# IOMOD-AD5593R-v2_0.net
KiCad netlist of a schematic drawn in EAGLE
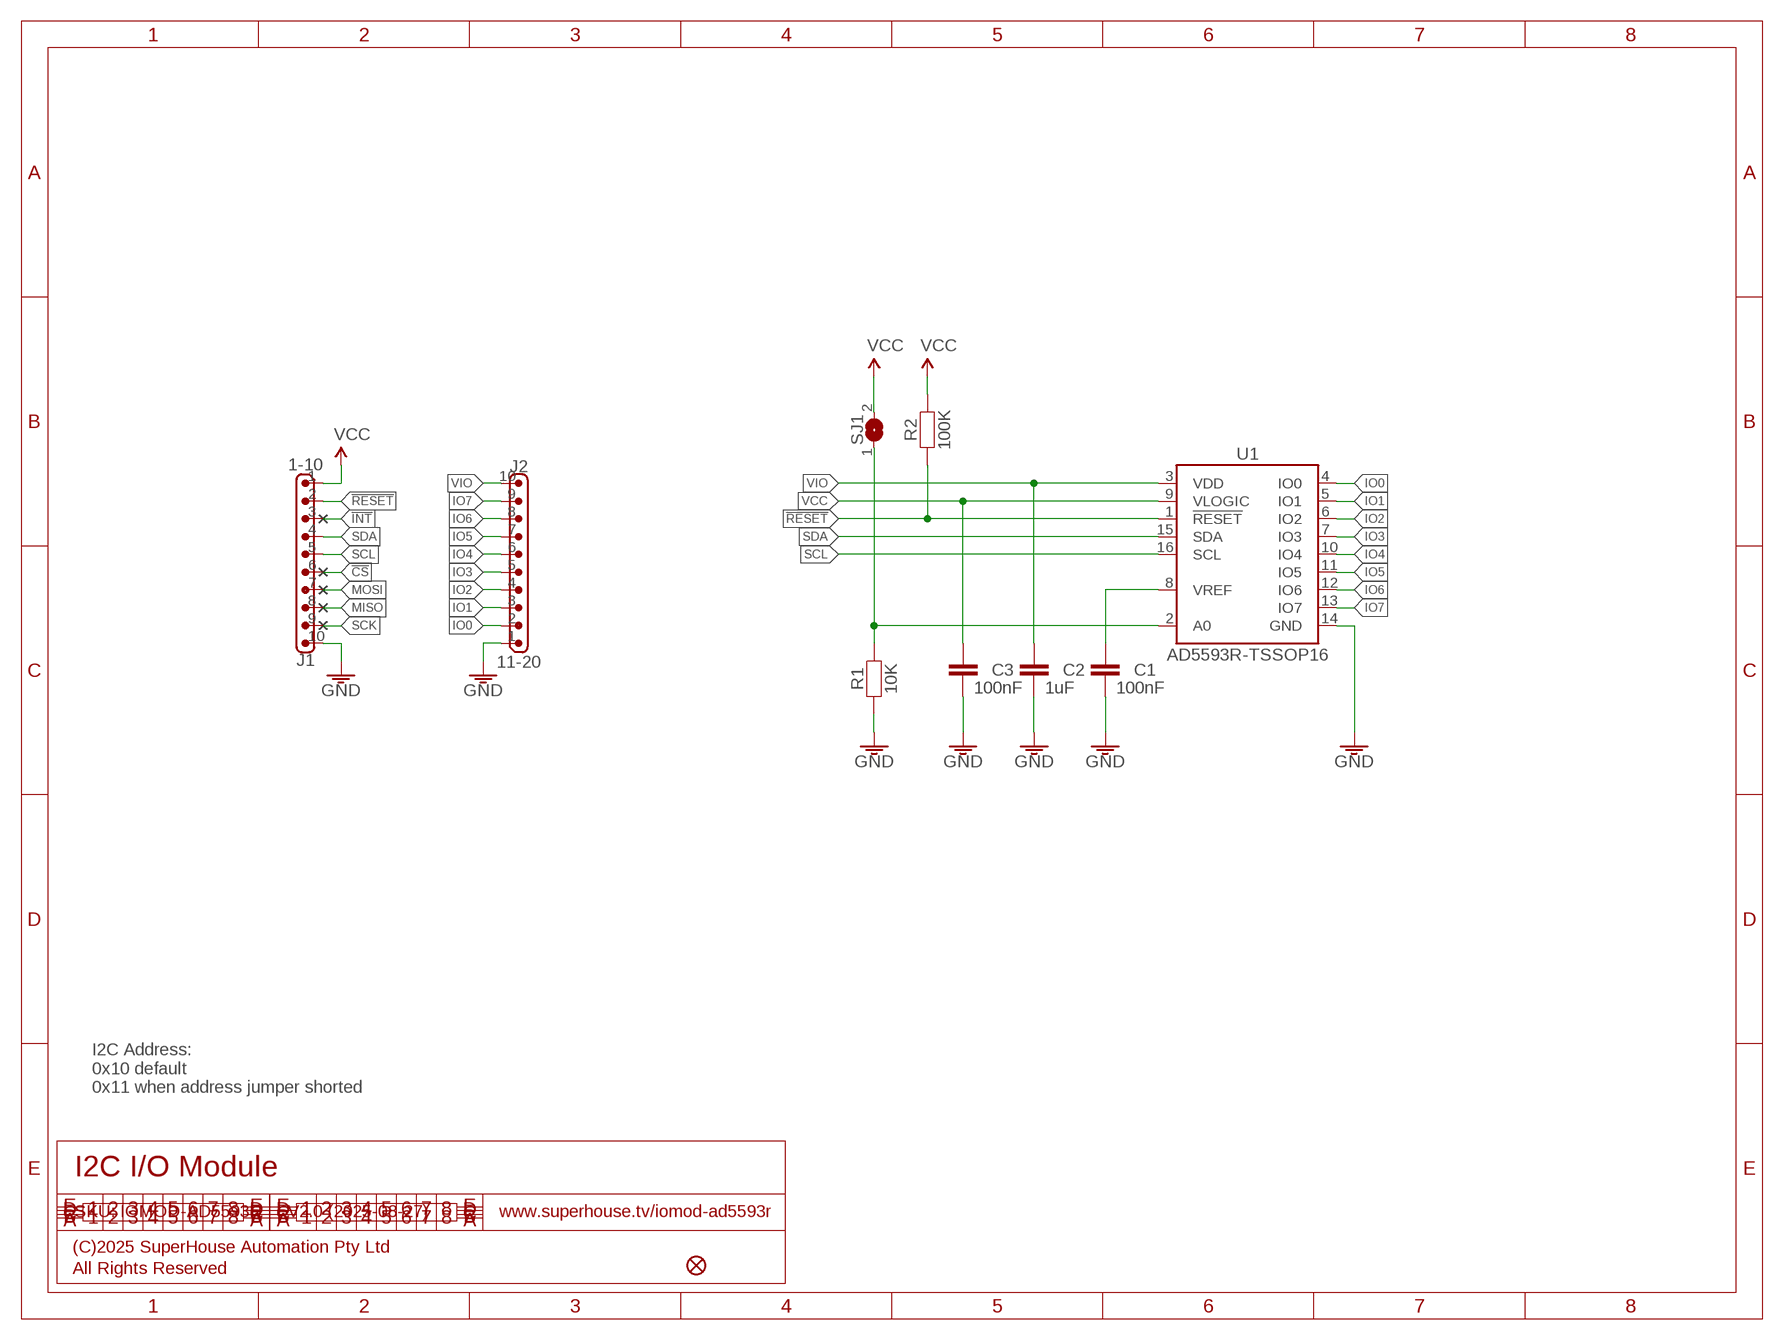
[diagram p0: schematic, sheet 1]

(export (version "E")
  (design (tool "Eeschema 10.0.6"))
  (components
    (comp (ref "C1")
      (value "100nF")
      (footprint "eagle-import:C0603")
      (libsource (lib "eagle-import") (part "CAP0603"))
    )
    (comp (ref "C2")
      (value "1uF")
      (footprint "eagle-import:C0603")
      (libsource (lib "eagle-import") (part "CAP0603"))
    )
    (comp (ref "C3")
      (value "100nF")
      (footprint "eagle-import:C0603")
      (libsource (lib "eagle-import") (part "CAP0603"))
    )
    (comp (ref "FID1")
      (value "FIDUCIAL1X2.5")
      (footprint "eagle-import:FIDUCIAL-1X2.5")
      (libsource (lib "eagle-import") (part "FIDUCIAL1X2.5"))
    )
    (comp (ref "J1")
      (value "1-10")
      (footprint "eagle-import:1X10-2.00-P-ABOVE")
      (libsource (lib "eagle-import") (part "M10-2.00-P-ABOVE"))
    )
    (comp (ref "J2")
      (value "11-20")
      (footprint "eagle-import:1X10-2.00-P-ABOVE")
      (libsource (lib "eagle-import") (part "M10-2.00-P-ABOVE"))
    )
    (comp (ref "R1")
      (value "10K")
      (footprint "eagle-import:R0603")
      (libsource (lib "eagle-import") (part "RESISTOR0603"))
    )
    (comp (ref "R2")
      (value "100K")
      (footprint "eagle-import:R0603")
      (libsource (lib "eagle-import") (part "RESISTOR0603"))
    )
    (comp (ref "SJ1")
      (value "SJ-NORMAL")
      (footprint "eagle-import:SJ")
      (libsource (lib "eagle-import") (part "SJ-NORMAL"))
    )
    (comp (ref "U1")
      (value "AD5593R-TSSOP16")
      (footprint "eagle-import:TSSOP16")
      (libsource (lib "eagle-import") (part "AD5593R-TSSOP16"))
    )
  )
  (nets
    (net (code "1") (name "/~{CS}") (class "Default")
      (node (ref "J1") (pin "6") (pinfunction "6_6") (pintype "passive"))
    )
    (net (code "2") (name "/~{INT}") (class "Default")
      (node (ref "J1") (pin "3") (pinfunction "3_3") (pintype "passive"))
    )
    (net (code "3") (name "/~{RESET}") (class "Default")
      (node (ref "J1") (pin "2") (pinfunction "2_2") (pintype "passive"))
      (node (ref "R2") (pin "1") (pinfunction "1_1") (pintype "passive"))
      (node (ref "U1") (pin "1") (pinfunction "~{RESET}_1") (pintype "passive"))
    )
    (net (code "4") (name "GND") (class "Default")
      (node (ref "C1") (pin "2") (pinfunction "2_2") (pintype "passive"))
      (node (ref "C2") (pin "2") (pinfunction "2_2") (pintype "passive"))
      (node (ref "C3") (pin "2") (pinfunction "2_2") (pintype "passive"))
      (node (ref "J1") (pin "10") (pinfunction "10_10") (pintype "passive"))
      (node (ref "J2") (pin "1") (pinfunction "1_1") (pintype "passive"))
      (node (ref "R1") (pin "1") (pinfunction "1_1") (pintype "passive"))
      (node (ref "U1") (pin "14") (pinfunction "GND_14") (pintype "passive"))
    )
    (net (code "5") (name "IO0") (class "Default")
      (node (ref "J2") (pin "2") (pinfunction "2_2") (pintype "passive"))
      (node (ref "U1") (pin "4") (pinfunction "IO0_4") (pintype "passive"))
    )
    (net (code "6") (name "IO1") (class "Default")
      (node (ref "J2") (pin "3") (pinfunction "3_3") (pintype "passive"))
      (node (ref "U1") (pin "5") (pinfunction "IO1_5") (pintype "passive"))
    )
    (net (code "7") (name "IO2") (class "Default")
      (node (ref "J2") (pin "4") (pinfunction "4_4") (pintype "passive"))
      (node (ref "U1") (pin "6") (pinfunction "IO2_6") (pintype "passive"))
    )
    (net (code "8") (name "IO3") (class "Default")
      (node (ref "J2") (pin "5") (pinfunction "5_5") (pintype "passive"))
      (node (ref "U1") (pin "7") (pinfunction "IO3_7") (pintype "passive"))
    )
    (net (code "9") (name "IO4") (class "Default")
      (node (ref "J2") (pin "6") (pinfunction "6_6") (pintype "passive"))
      (node (ref "U1") (pin "10") (pinfunction "IO4_10") (pintype "passive"))
    )
    (net (code "10") (name "IO5") (class "Default")
      (node (ref "J2") (pin "7") (pinfunction "7_7") (pintype "passive"))
      (node (ref "U1") (pin "11") (pinfunction "IO5_11") (pintype "passive"))
    )
    (net (code "11") (name "IO6") (class "Default")
      (node (ref "J2") (pin "8") (pinfunction "8_8") (pintype "passive"))
      (node (ref "U1") (pin "12") (pinfunction "IO6_12") (pintype "passive"))
    )
    (net (code "12") (name "IO7") (class "Default")
      (node (ref "J2") (pin "9") (pinfunction "9_9") (pintype "passive"))
      (node (ref "U1") (pin "13") (pinfunction "IO7_13") (pintype "passive"))
    )
    (net (code "13") (name "MISO") (class "Default")
      (node (ref "J1") (pin "8") (pinfunction "8_8") (pintype "passive"))
    )
    (net (code "14") (name "MOSI") (class "Default")
      (node (ref "J1") (pin "7") (pinfunction "7_7") (pintype "passive"))
    )
    (net (code "15") (name "Net-(U1-A0)") (class "Default")
      (node (ref "R1") (pin "2") (pinfunction "2_2") (pintype "passive"))
      (node (ref "SJ1") (pin "1") (pinfunction "1_1") (pintype "passive"))
      (node (ref "U1") (pin "2") (pinfunction "A0_2") (pintype "passive"))
    )
    (net (code "16") (name "Net-(U1-VREF)") (class "Default")
      (node (ref "C1") (pin "1") (pinfunction "1_1") (pintype "passive"))
      (node (ref "U1") (pin "8") (pinfunction "VREF_8") (pintype "passive"))
    )
    (net (code "17") (name "SCK") (class "Default")
      (node (ref "J1") (pin "9") (pinfunction "9_9") (pintype "passive"))
    )
    (net (code "18") (name "SCL") (class "Default")
      (node (ref "J1") (pin "5") (pinfunction "5_5") (pintype "passive"))
      (node (ref "U1") (pin "16") (pinfunction "SCL_16") (pintype "passive"))
    )
    (net (code "19") (name "SDA") (class "Default")
      (node (ref "J1") (pin "4") (pinfunction "4_4") (pintype "passive"))
      (node (ref "U1") (pin "15") (pinfunction "SDA_15") (pintype "passive"))
    )
    (net (code "20") (name "VCC") (class "Default")
      (node (ref "C3") (pin "1") (pinfunction "1_1") (pintype "passive"))
      (node (ref "J1") (pin "1") (pinfunction "1_1") (pintype "passive"))
      (node (ref "R2") (pin "2") (pinfunction "2_2") (pintype "passive"))
      (node (ref "SJ1") (pin "2") (pinfunction "2_2") (pintype "passive"))
      (node (ref "U1") (pin "9") (pinfunction "VLOGIC_9") (pintype "passive"))
    )
    (net (code "21") (name "VIO") (class "Default")
      (node (ref "C2") (pin "1") (pinfunction "1_1") (pintype "passive"))
      (node (ref "J2") (pin "10") (pinfunction "10_10") (pintype "passive"))
      (node (ref "U1") (pin "3") (pinfunction "VDD_3") (pintype "passive"))
    )
  )
)
